# breakout_STM32F042F6P6.net
KiCad netlist of a schematic drawn in EAGLE
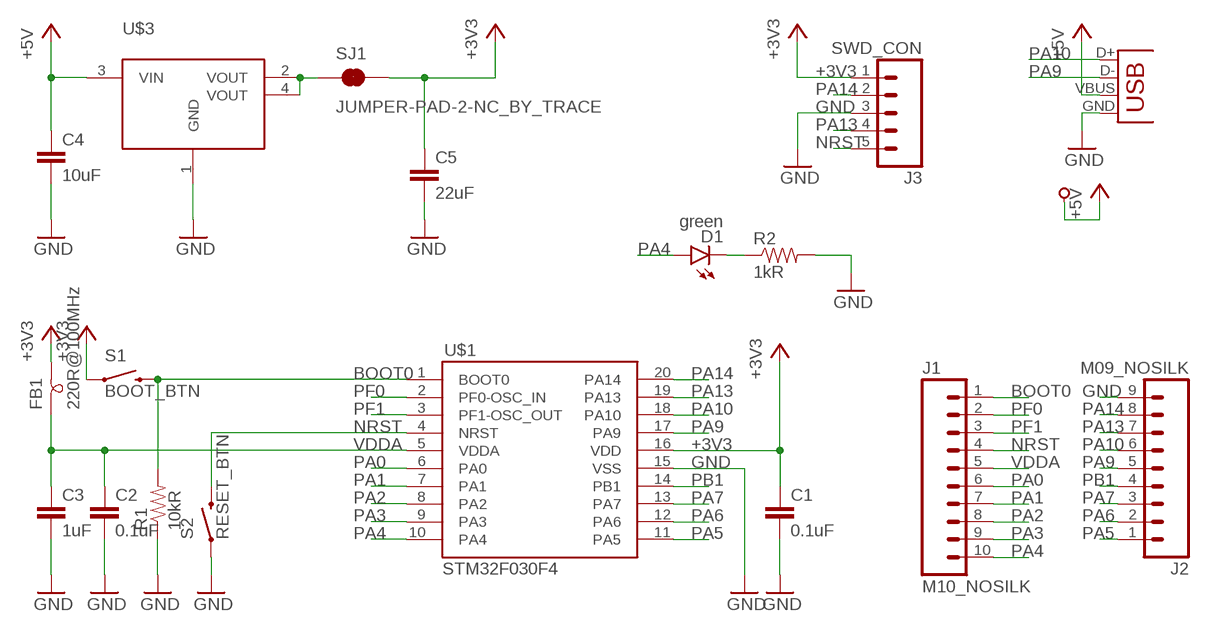
[diagram p0: schematic, sheet 1]

(export (version "E")
  (design (tool "Eeschema 10.0.6"))
  (components
    (comp (ref "C1")
      (value "0.1uF")
      (footprint "eagle-import:0805")
      (libsource (lib "eagle-import") (part "CAPACITOR0805"))
    )
    (comp (ref "C2")
      (value "0.1uF")
      (footprint "eagle-import:0805")
      (libsource (lib "eagle-import") (part "CAPACITOR0805"))
    )
    (comp (ref "C3")
      (value "1uF")
      (footprint "eagle-import:0805")
      (libsource (lib "eagle-import") (part "CAPACITOR0805"))
    )
    (comp (ref "C4")
      (value "10uF")
      (footprint "eagle-import:0805")
      (libsource (lib "eagle-import") (part "CAPACITOR0805"))
    )
    (comp (ref "C5")
      (value "22uF")
      (footprint "eagle-import:0805")
      (libsource (lib "eagle-import") (part "CAPACITOR0805"))
    )
    (comp (ref "D1")
      (value "green")
      (footprint "eagle-import:LED-805")
      (libsource (lib "eagle-import") (part "LED805"))
    )
    (comp (ref "FB1")
      (value "220R@100MHz")
      (footprint "eagle-import:0805")
      (libsource (lib "eagle-import") (part "FERRITE-BEAD0805"))
    )
    (comp (ref "J1")
      (value "M10_NOSILK")
      (footprint "eagle-import:M10_NOSILK")
      (libsource (lib "eagle-import") (part "M10_NOSILK"))
    )
    (comp (ref "J2")
      (value "M09_NOSILK")
      (footprint "eagle-import:M09_NOSILK")
      (libsource (lib "eagle-import") (part "M09_NOSILK"))
    )
    (comp (ref "J3")
      (value "SWD_CON")
      (footprint "eagle-import:M05_NOSILK_1SQ")
      (libsource (lib "eagle-import") (part "M05_NOSILK_1SQ"))
    )
    (comp (ref "JP1")
      (value "USBSMD")
      (footprint "eagle-import:USB-MINIB")
      (libsource (lib "eagle-import") (part "USBSMD"))
    )
    (comp (ref "R1")
      (value "10kR")
      (footprint "eagle-import:0805")
      (libsource (lib "eagle-import") (part "RESISTOR0805"))
    )
    (comp (ref "R2")
      (value "1kR")
      (footprint "eagle-import:0805")
      (libsource (lib "eagle-import") (part "RESISTOR0805"))
    )
    (comp (ref "S1")
      (value "BOOT_BTN")
      (footprint "eagle-import:TACTILE-SWITCH-1101NE")
      (libsource (lib "eagle-import") (part "SWITCH-MOMENTARY-2-SMD-1101NE"))
    )
    (comp (ref "S2")
      (value "RESET_BTN")
      (footprint "eagle-import:TACTILE-SWITCH-1101NE")
      (libsource (lib "eagle-import") (part "SWITCH-MOMENTARY-2-SMD-1101NE"))
    )
    (comp (ref "SJ1")
      (value "JUMPER-PAD-2-NC_BY_TRACE")
      (footprint "eagle-import:PAD-JUMPER-2-NC_BY_TRACE_YES_SILK")
      (libsource (lib "eagle-import") (part "JUMPER-PAD-2-NC_BY_TRACE"))
    )
    (comp (ref "U$1")
      (value "STM32F030F4")
      (footprint "eagle-import:TSSOP-20")
      (libsource (lib "eagle-import") (part "STM32F030F4"))
    )
    (comp (ref "U$2")
      (value "M01_1SQ")
      (footprint "eagle-import:M01_1SQ")
      (libsource (lib "eagle-import") (part "M01_1SQ"))
    )
    (comp (ref "U$3")
      (value "AMS1117_SOT223")
      (footprint "eagle-import:SOT223")
      (libsource (lib "eagle-import") (part "AMS1117_SOT223"))
    )
  )
  (nets
    (net (code "1") (name "+3V3") (class "Default")
      (node (ref "C1") (pin "1") (pinfunction "1_1") (pintype "passive"))
      (node (ref "C5") (pin "1") (pinfunction "1_1") (pintype "passive"))
      (node (ref "FB1") (pin "2") (pinfunction "2_2") (pintype "passive"))
      (node (ref "J3") (pin "1") (pinfunction "1_1") (pintype "passive"))
      (node (ref "S1") (pin "1") (pinfunction "1_1") (pintype "passive"))
      (node (ref "SJ1") (pin "2") (pinfunction "2_2") (pintype "passive"))
      (node (ref "U$1") (pin "16") (pinfunction "VDD_16") (pintype "bidirectional"))
    )
    (net (code "2") (name "+5V") (class "Default")
      (node (ref "C4") (pin "1") (pinfunction "1_1") (pintype "passive"))
      (node (ref "JP1") (pin "VBUS") (pinfunction "VBUS_VBUS") (pintype "bidirectional"))
      (node (ref "U$2") (pin "1") (pinfunction "1_1") (pintype "bidirectional"))
      (node (ref "U$3") (pin "3") (pinfunction "VIN_3") (pintype "bidirectional"))
    )
    (net (code "3") (name "/BOOT0") (class "Default")
      (node (ref "J1") (pin "1") (pinfunction "1_1") (pintype "passive"))
      (node (ref "R1") (pin "2") (pinfunction "2_2") (pintype "passive"))
      (node (ref "S1") (pin "2") (pinfunction "2_2") (pintype "passive"))
      (node (ref "U$1") (pin "1") (pinfunction "BOOT0_1") (pintype "bidirectional"))
    )
    (net (code "4") (name "/NRST") (class "Default")
      (node (ref "J1") (pin "4") (pinfunction "4_4") (pintype "passive"))
      (node (ref "J3") (pin "5") (pinfunction "5_5") (pintype "passive"))
      (node (ref "S2") (pin "2") (pinfunction "2_2") (pintype "passive"))
      (node (ref "U$1") (pin "4") (pinfunction "NRST_4") (pintype "bidirectional"))
    )
    (net (code "5") (name "/PA0") (class "Default")
      (node (ref "J1") (pin "6") (pinfunction "6_6") (pintype "passive"))
      (node (ref "U$1") (pin "6") (pinfunction "PA0_6") (pintype "bidirectional"))
    )
    (net (code "6") (name "/PA1") (class "Default")
      (node (ref "J1") (pin "7") (pinfunction "7_7") (pintype "passive"))
      (node (ref "U$1") (pin "7") (pinfunction "PA1_7") (pintype "bidirectional"))
    )
    (net (code "7") (name "/PA2") (class "Default")
      (node (ref "J1") (pin "8") (pinfunction "8_8") (pintype "passive"))
      (node (ref "U$1") (pin "8") (pinfunction "PA2_8") (pintype "bidirectional"))
    )
    (net (code "8") (name "/PA3") (class "Default")
      (node (ref "J1") (pin "9") (pinfunction "9_9") (pintype "passive"))
      (node (ref "U$1") (pin "9") (pinfunction "PA3_9") (pintype "bidirectional"))
    )
    (net (code "9") (name "/PA4") (class "Default")
      (node (ref "D1") (pin "A") (pinfunction "A_A") (pintype "passive"))
      (node (ref "J1") (pin "10") (pinfunction "10_10") (pintype "passive"))
      (node (ref "U$1") (pin "10") (pinfunction "PA4_10") (pintype "bidirectional"))
    )
    (net (code "10") (name "/PA5") (class "Default")
      (node (ref "J2") (pin "1") (pinfunction "1_1") (pintype "passive"))
      (node (ref "U$1") (pin "11") (pinfunction "PA5_11") (pintype "bidirectional"))
    )
    (net (code "11") (name "/PA6") (class "Default")
      (node (ref "J2") (pin "2") (pinfunction "2_2") (pintype "passive"))
      (node (ref "U$1") (pin "12") (pinfunction "PA6_12") (pintype "bidirectional"))
    )
    (net (code "12") (name "/PA7") (class "Default")
      (node (ref "J2") (pin "3") (pinfunction "3_3") (pintype "passive"))
      (node (ref "U$1") (pin "13") (pinfunction "PA7_13") (pintype "bidirectional"))
    )
    (net (code "13") (name "/PA9") (class "Default")
      (node (ref "J2") (pin "5") (pinfunction "5_5") (pintype "passive"))
      (node (ref "JP1") (pin "D-") (pinfunction "D-_D-") (pintype "bidirectional"))
      (node (ref "U$1") (pin "17") (pinfunction "PA9_17") (pintype "bidirectional"))
    )
    (net (code "14") (name "/PA10") (class "Default")
      (node (ref "J2") (pin "6") (pinfunction "6_6") (pintype "passive"))
      (node (ref "JP1") (pin "D+") (pinfunction "D+_D+") (pintype "bidirectional"))
      (node (ref "U$1") (pin "18") (pinfunction "PA10_18") (pintype "bidirectional"))
    )
    (net (code "15") (name "/PA13") (class "Default")
      (node (ref "J2") (pin "7") (pinfunction "7_7") (pintype "passive"))
      (node (ref "J3") (pin "4") (pinfunction "4_4") (pintype "passive"))
      (node (ref "U$1") (pin "19") (pinfunction "PA13_19") (pintype "bidirectional"))
    )
    (net (code "16") (name "/PA14") (class "Default")
      (node (ref "J2") (pin "8") (pinfunction "8_8") (pintype "passive"))
      (node (ref "J3") (pin "2") (pinfunction "2_2") (pintype "passive"))
      (node (ref "U$1") (pin "20") (pinfunction "PA14_20") (pintype "bidirectional"))
    )
    (net (code "17") (name "/PB1") (class "Default")
      (node (ref "J2") (pin "4") (pinfunction "4_4") (pintype "passive"))
      (node (ref "U$1") (pin "14") (pinfunction "PB1_14") (pintype "bidirectional"))
    )
    (net (code "18") (name "/PF0") (class "Default")
      (node (ref "J1") (pin "2") (pinfunction "2_2") (pintype "passive"))
      (node (ref "U$1") (pin "2") (pinfunction "PF0-OSC_IN_2") (pintype "bidirectional"))
    )
    (net (code "19") (name "/PF1") (class "Default")
      (node (ref "J1") (pin "3") (pinfunction "3_3") (pintype "passive"))
      (node (ref "U$1") (pin "3") (pinfunction "PF1-OSC_OUT_3") (pintype "bidirectional"))
    )
    (net (code "20") (name "/VDDA") (class "Default")
      (node (ref "C2") (pin "1") (pinfunction "1_1") (pintype "passive"))
      (node (ref "C3") (pin "1") (pinfunction "1_1") (pintype "passive"))
      (node (ref "FB1") (pin "1") (pinfunction "1_1") (pintype "passive"))
      (node (ref "J1") (pin "5") (pinfunction "5_5") (pintype "passive"))
      (node (ref "U$1") (pin "5") (pinfunction "VDDA_5") (pintype "bidirectional"))
    )
    (net (code "21") (name "GND") (class "Default")
      (node (ref "C1") (pin "2") (pinfunction "2_2") (pintype "passive"))
      (node (ref "C2") (pin "2") (pinfunction "2_2") (pintype "passive"))
      (node (ref "C3") (pin "2") (pinfunction "2_2") (pintype "passive"))
      (node (ref "C4") (pin "2") (pinfunction "2_2") (pintype "passive"))
      (node (ref "C5") (pin "2") (pinfunction "2_2") (pintype "passive"))
      (node (ref "J2") (pin "9") (pinfunction "9_9") (pintype "passive"))
      (node (ref "J3") (pin "3") (pinfunction "3_3") (pintype "passive"))
      (node (ref "JP1") (pin "GND") (pinfunction "GND_GND") (pintype "bidirectional"))
      (node (ref "R1") (pin "1") (pinfunction "1_1") (pintype "passive"))
      (node (ref "R2") (pin "2") (pinfunction "2_2") (pintype "passive"))
      (node (ref "S2") (pin "1") (pinfunction "1_1") (pintype "passive"))
      (node (ref "U$1") (pin "15") (pinfunction "VSS_15") (pintype "bidirectional"))
      (node (ref "U$3") (pin "1") (pinfunction "GND_1") (pintype "bidirectional"))
    )
    (net (code "22") (name "Net-(D1-PadC)") (class "Default")
      (node (ref "D1") (pin "C") (pinfunction "C_C") (pintype "passive"))
      (node (ref "R2") (pin "1") (pinfunction "1_1") (pintype "passive"))
    )
    (net (code "23") (name "Net-(SJ1-Pad1)") (class "Default")
      (node (ref "SJ1") (pin "1") (pinfunction "1_1") (pintype "passive"))
      (node (ref "U$3") (pin "2") (pinfunction "VOUT_2") (pintype "bidirectional"))
      (node (ref "U$3") (pin "4") (pinfunction "VOUT_4") (pintype "bidirectional"))
    )
  )
)
